# wordclock-ledboard.net
KiCad netlist of a schematic drawn in EAGLE
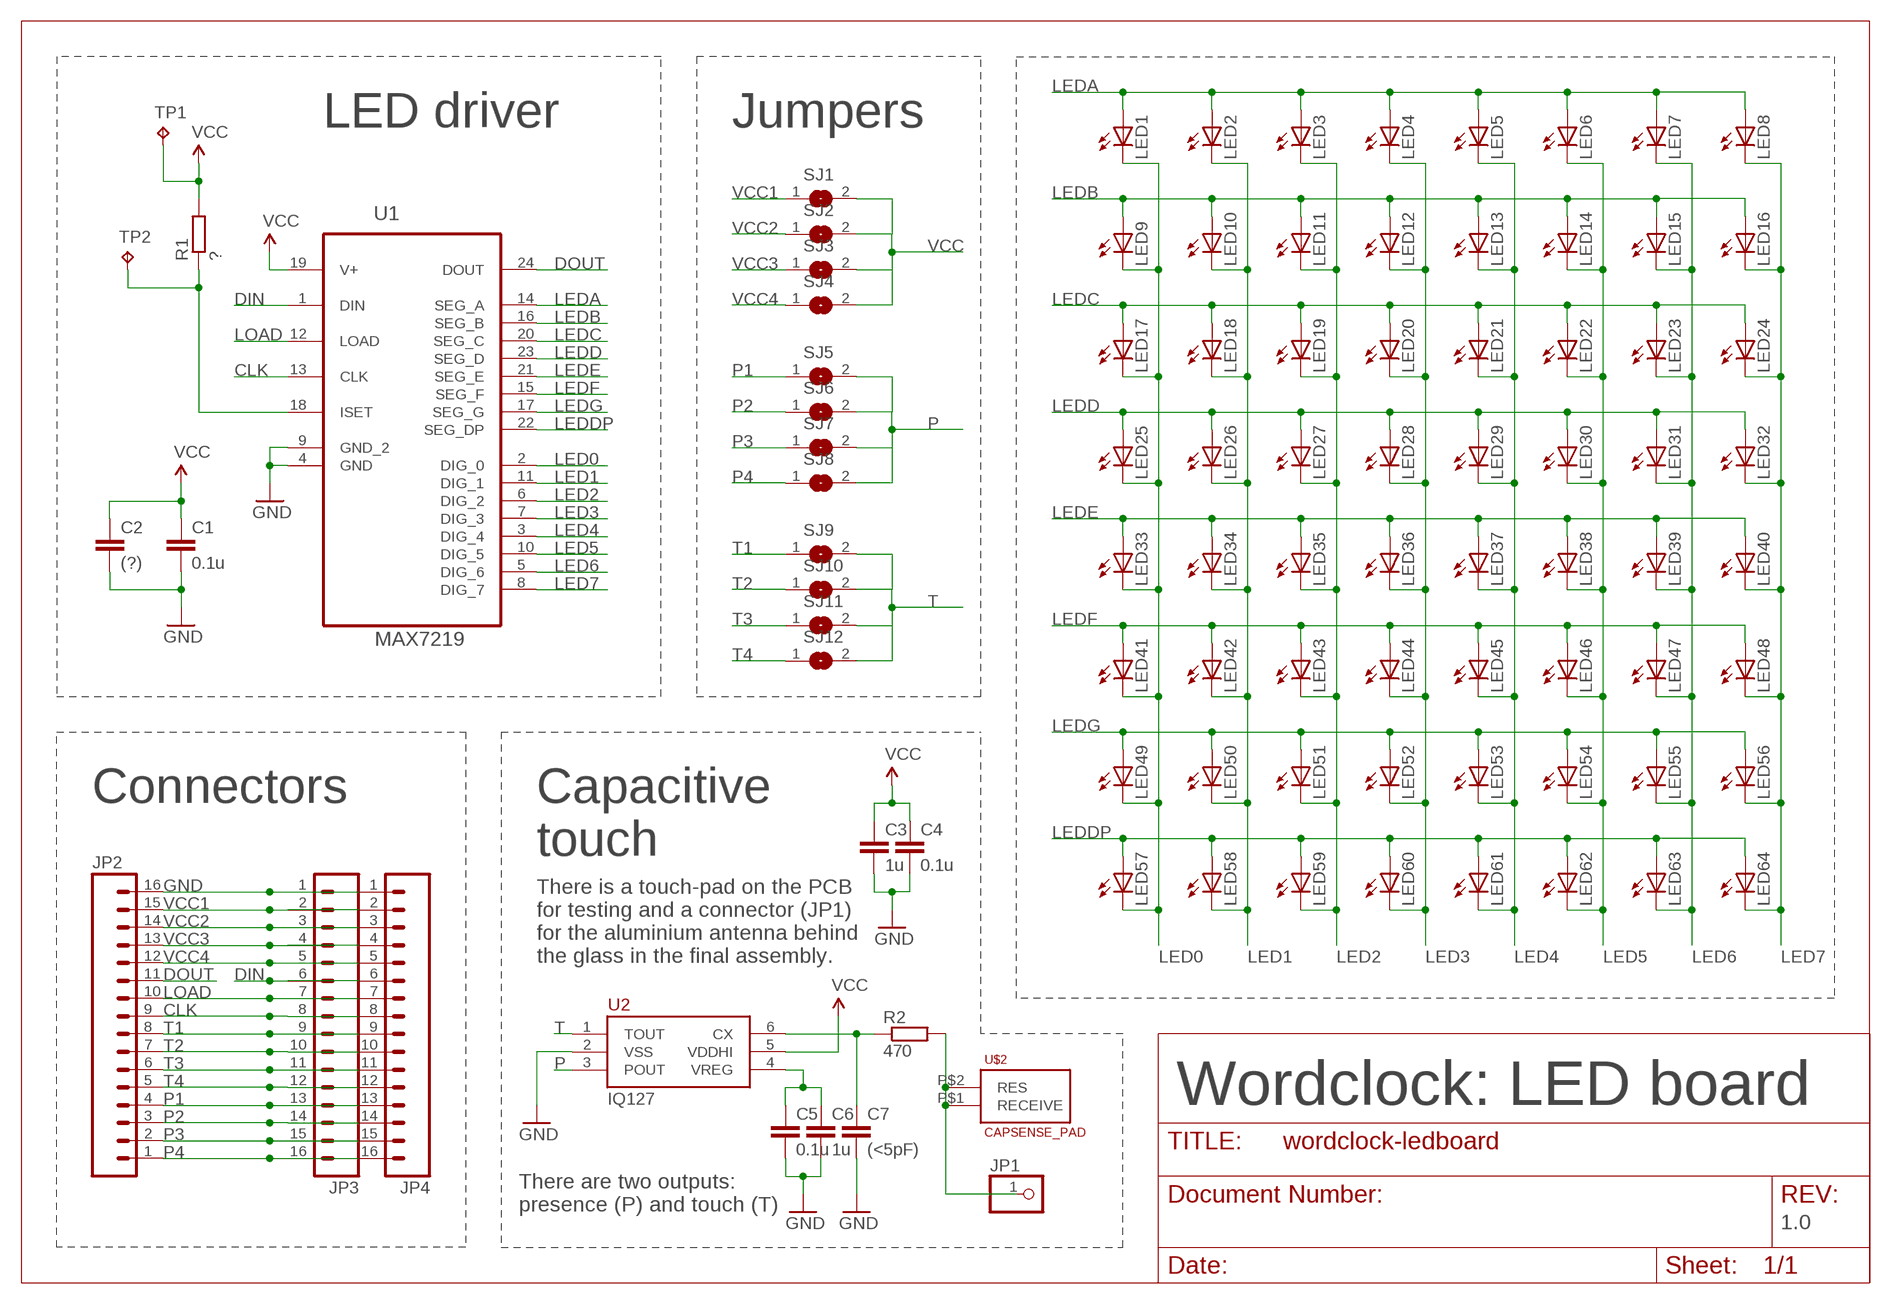
[diagram p0: schematic, sheet 1]

(export (version "E")
  (design (tool "Eeschema 10.0.6"))
  (components
    (comp (ref "C1")
      (value "0.1u")
      (footprint "eagle-import:C0805")
      (libsource (lib "eagle-import") (part "C-EUC0805"))
    )
    (comp (ref "C2")
      (value "(?)")
      (footprint "eagle-import:C0805")
      (libsource (lib "eagle-import") (part "C-EUC0805"))
    )
    (comp (ref "C3")
      (value "1u")
      (footprint "eagle-import:C0805")
      (libsource (lib "eagle-import") (part "C-EUC0805"))
    )
    (comp (ref "C4")
      (value "0.1u")
      (footprint "eagle-import:C0805")
      (libsource (lib "eagle-import") (part "C-EUC0805"))
    )
    (comp (ref "C5")
      (value "0.1u")
      (footprint "eagle-import:C0805")
      (libsource (lib "eagle-import") (part "C-EUC0805"))
    )
    (comp (ref "C6")
      (value "1u")
      (footprint "eagle-import:C0805")
      (libsource (lib "eagle-import") (part "C-EUC0805"))
    )
    (comp (ref "C7")
      (value "(<5pF)")
      (footprint "eagle-import:C0805")
      (libsource (lib "eagle-import") (part "C-EUC0805"))
    )
    (comp (ref "JP1")
      (value "PINHD-1X1")
      (footprint "eagle-import:1X01")
      (libsource (lib "eagle-import") (part "PINHD-1X1"))
    )
    (comp (ref "JP2")
      (value "M161X16_NO_SILK")
      (footprint "eagle-import:1X16_NO_SILK")
      (libsource (lib "eagle-import") (part "M161X16_NO_SILK"))
    )
    (comp (ref "JP3")
      (value "M161X16_NO_SILK")
      (footprint "eagle-import:1X16_NO_SILK")
      (libsource (lib "eagle-import") (part "M161X16_NO_SILK"))
    )
    (comp (ref "JP4")
      (value "M161X16_NO_SILK")
      (footprint "eagle-import:1X16_NO_SILK")
      (libsource (lib "eagle-import") (part "M161X16_NO_SILK"))
    )
    (comp (ref "LED1")
      (value "LEDKA-3528ASYC")
      (footprint "eagle-import:KA-3528ASYC")
      (libsource (lib "eagle-import") (part "LEDKA-3528ASYC"))
    )
    (comp (ref "LED2")
      (value "LEDKA-3528ASYC")
      (footprint "eagle-import:KA-3528ASYC")
      (libsource (lib "eagle-import") (part "LEDKA-3528ASYC"))
    )
    (comp (ref "LED3")
      (value "LEDKA-3528ASYC")
      (footprint "eagle-import:KA-3528ASYC")
      (libsource (lib "eagle-import") (part "LEDKA-3528ASYC"))
    )
    (comp (ref "LED4")
      (value "LEDKA-3528ASYC")
      (footprint "eagle-import:KA-3528ASYC")
      (libsource (lib "eagle-import") (part "LEDKA-3528ASYC"))
    )
    (comp (ref "LED5")
      (value "LEDKA-3528ASYC")
      (footprint "eagle-import:KA-3528ASYC")
      (libsource (lib "eagle-import") (part "LEDKA-3528ASYC"))
    )
    (comp (ref "LED6")
      (value "LEDKA-3528ASYC")
      (footprint "eagle-import:KA-3528ASYC")
      (libsource (lib "eagle-import") (part "LEDKA-3528ASYC"))
    )
    (comp (ref "LED7")
      (value "LEDKA-3528ASYC")
      (footprint "eagle-import:KA-3528ASYC")
      (libsource (lib "eagle-import") (part "LEDKA-3528ASYC"))
    )
    (comp (ref "LED8")
      (value "LEDKA-3528ASYC")
      (footprint "eagle-import:KA-3528ASYC")
      (libsource (lib "eagle-import") (part "LEDKA-3528ASYC"))
    )
    (comp (ref "LED9")
      (value "LEDKA-3528ASYC")
      (footprint "eagle-import:KA-3528ASYC")
      (libsource (lib "eagle-import") (part "LEDKA-3528ASYC"))
    )
    (comp (ref "LED10")
      (value "LEDKA-3528ASYC")
      (footprint "eagle-import:KA-3528ASYC")
      (libsource (lib "eagle-import") (part "LEDKA-3528ASYC"))
    )
    (comp (ref "LED11")
      (value "LEDKA-3528ASYC")
      (footprint "eagle-import:KA-3528ASYC")
      (libsource (lib "eagle-import") (part "LEDKA-3528ASYC"))
    )
    (comp (ref "LED12")
      (value "LEDKA-3528ASYC")
      (footprint "eagle-import:KA-3528ASYC")
      (libsource (lib "eagle-import") (part "LEDKA-3528ASYC"))
    )
    (comp (ref "LED13")
      (value "LEDKA-3528ASYC")
      (footprint "eagle-import:KA-3528ASYC")
      (libsource (lib "eagle-import") (part "LEDKA-3528ASYC"))
    )
    (comp (ref "LED14")
      (value "LEDKA-3528ASYC")
      (footprint "eagle-import:KA-3528ASYC")
      (libsource (lib "eagle-import") (part "LEDKA-3528ASYC"))
    )
    (comp (ref "LED15")
      (value "LEDKA-3528ASYC")
      (footprint "eagle-import:KA-3528ASYC")
      (libsource (lib "eagle-import") (part "LEDKA-3528ASYC"))
    )
    (comp (ref "LED16")
      (value "LEDKA-3528ASYC")
      (footprint "eagle-import:KA-3528ASYC")
      (libsource (lib "eagle-import") (part "LEDKA-3528ASYC"))
    )
    (comp (ref "LED17")
      (value "LEDKA-3528ASYC")
      (footprint "eagle-import:KA-3528ASYC")
      (libsource (lib "eagle-import") (part "LEDKA-3528ASYC"))
    )
    (comp (ref "LED18")
      (value "LEDKA-3528ASYC")
      (footprint "eagle-import:KA-3528ASYC")
      (libsource (lib "eagle-import") (part "LEDKA-3528ASYC"))
    )
    (comp (ref "LED19")
      (value "LEDKA-3528ASYC")
      (footprint "eagle-import:KA-3528ASYC")
      (libsource (lib "eagle-import") (part "LEDKA-3528ASYC"))
    )
    (comp (ref "LED20")
      (value "LEDKA-3528ASYC")
      (footprint "eagle-import:KA-3528ASYC")
      (libsource (lib "eagle-import") (part "LEDKA-3528ASYC"))
    )
    (comp (ref "LED21")
      (value "LEDKA-3528ASYC")
      (footprint "eagle-import:KA-3528ASYC")
      (libsource (lib "eagle-import") (part "LEDKA-3528ASYC"))
    )
    (comp (ref "LED22")
      (value "LEDKA-3528ASYC")
      (footprint "eagle-import:KA-3528ASYC")
      (libsource (lib "eagle-import") (part "LEDKA-3528ASYC"))
    )
    (comp (ref "LED23")
      (value "LEDKA-3528ASYC")
      (footprint "eagle-import:KA-3528ASYC")
      (libsource (lib "eagle-import") (part "LEDKA-3528ASYC"))
    )
    (comp (ref "LED24")
      (value "LEDKA-3528ASYC")
      (footprint "eagle-import:KA-3528ASYC")
      (libsource (lib "eagle-import") (part "LEDKA-3528ASYC"))
    )
    (comp (ref "LED25")
      (value "LEDKA-3528ASYC")
      (footprint "eagle-import:KA-3528ASYC")
      (libsource (lib "eagle-import") (part "LEDKA-3528ASYC"))
    )
    (comp (ref "LED26")
      (value "LEDKA-3528ASYC")
      (footprint "eagle-import:KA-3528ASYC")
      (libsource (lib "eagle-import") (part "LEDKA-3528ASYC"))
    )
    (comp (ref "LED27")
      (value "LEDKA-3528ASYC")
      (footprint "eagle-import:KA-3528ASYC")
      (libsource (lib "eagle-import") (part "LEDKA-3528ASYC"))
    )
    (comp (ref "LED28")
      (value "LEDKA-3528ASYC")
      (footprint "eagle-import:KA-3528ASYC")
      (libsource (lib "eagle-import") (part "LEDKA-3528ASYC"))
    )
    (comp (ref "LED29")
      (value "LEDKA-3528ASYC")
      (footprint "eagle-import:KA-3528ASYC")
      (libsource (lib "eagle-import") (part "LEDKA-3528ASYC"))
    )
    (comp (ref "LED30")
      (value "LEDKA-3528ASYC")
      (footprint "eagle-import:KA-3528ASYC")
      (libsource (lib "eagle-import") (part "LEDKA-3528ASYC"))
    )
    (comp (ref "LED31")
      (value "LEDKA-3528ASYC")
      (footprint "eagle-import:KA-3528ASYC")
      (libsource (lib "eagle-import") (part "LEDKA-3528ASYC"))
    )
    (comp (ref "LED32")
      (value "LEDKA-3528ASYC")
      (footprint "eagle-import:KA-3528ASYC")
      (libsource (lib "eagle-import") (part "LEDKA-3528ASYC"))
    )
    (comp (ref "LED33")
      (value "LEDKA-3528ASYC")
      (footprint "eagle-import:KA-3528ASYC")
      (libsource (lib "eagle-import") (part "LEDKA-3528ASYC"))
    )
    (comp (ref "LED34")
      (value "LEDKA-3528ASYC")
      (footprint "eagle-import:KA-3528ASYC")
      (libsource (lib "eagle-import") (part "LEDKA-3528ASYC"))
    )
    (comp (ref "LED35")
      (value "LEDKA-3528ASYC")
      (footprint "eagle-import:KA-3528ASYC")
      (libsource (lib "eagle-import") (part "LEDKA-3528ASYC"))
    )
    (comp (ref "LED36")
      (value "LEDKA-3528ASYC")
      (footprint "eagle-import:KA-3528ASYC")
      (libsource (lib "eagle-import") (part "LEDKA-3528ASYC"))
    )
    (comp (ref "LED37")
      (value "LEDKA-3528ASYC")
      (footprint "eagle-import:KA-3528ASYC")
      (libsource (lib "eagle-import") (part "LEDKA-3528ASYC"))
    )
    (comp (ref "LED38")
      (value "LEDKA-3528ASYC")
      (footprint "eagle-import:KA-3528ASYC")
      (libsource (lib "eagle-import") (part "LEDKA-3528ASYC"))
    )
    (comp (ref "LED39")
      (value "LEDKA-3528ASYC")
      (footprint "eagle-import:KA-3528ASYC")
      (libsource (lib "eagle-import") (part "LEDKA-3528ASYC"))
    )
    (comp (ref "LED40")
      (value "LEDKA-3528ASYC")
      (footprint "eagle-import:KA-3528ASYC")
      (libsource (lib "eagle-import") (part "LEDKA-3528ASYC"))
    )
    (comp (ref "LED41")
      (value "LEDKA-3528ASYC")
      (footprint "eagle-import:KA-3528ASYC")
      (libsource (lib "eagle-import") (part "LEDKA-3528ASYC"))
    )
    (comp (ref "LED42")
      (value "LEDKA-3528ASYC")
      (footprint "eagle-import:KA-3528ASYC")
      (libsource (lib "eagle-import") (part "LEDKA-3528ASYC"))
    )
    (comp (ref "LED43")
      (value "LEDKA-3528ASYC")
      (footprint "eagle-import:KA-3528ASYC")
      (libsource (lib "eagle-import") (part "LEDKA-3528ASYC"))
    )
    (comp (ref "LED44")
      (value "LEDKA-3528ASYC")
      (footprint "eagle-import:KA-3528ASYC")
      (libsource (lib "eagle-import") (part "LEDKA-3528ASYC"))
    )
    (comp (ref "LED45")
      (value "LEDKA-3528ASYC")
      (footprint "eagle-import:KA-3528ASYC")
      (libsource (lib "eagle-import") (part "LEDKA-3528ASYC"))
    )
    (comp (ref "LED46")
      (value "LEDKA-3528ASYC")
      (footprint "eagle-import:KA-3528ASYC")
      (libsource (lib "eagle-import") (part "LEDKA-3528ASYC"))
    )
    (comp (ref "LED47")
      (value "LEDKA-3528ASYC")
      (footprint "eagle-import:KA-3528ASYC")
      (libsource (lib "eagle-import") (part "LEDKA-3528ASYC"))
    )
    (comp (ref "LED48")
      (value "LEDKA-3528ASYC")
      (footprint "eagle-import:KA-3528ASYC")
      (libsource (lib "eagle-import") (part "LEDKA-3528ASYC"))
    )
    (comp (ref "LED49")
      (value "LEDKA-3528ASYC")
      (footprint "eagle-import:KA-3528ASYC")
      (libsource (lib "eagle-import") (part "LEDKA-3528ASYC"))
    )
    (comp (ref "LED50")
      (value "LEDKA-3528ASYC")
      (footprint "eagle-import:KA-3528ASYC")
      (libsource (lib "eagle-import") (part "LEDKA-3528ASYC"))
    )
    (comp (ref "LED51")
      (value "LEDKA-3528ASYC")
      (footprint "eagle-import:KA-3528ASYC")
      (libsource (lib "eagle-import") (part "LEDKA-3528ASYC"))
    )
    (comp (ref "LED52")
      (value "LEDKA-3528ASYC")
      (footprint "eagle-import:KA-3528ASYC")
      (libsource (lib "eagle-import") (part "LEDKA-3528ASYC"))
    )
    (comp (ref "LED53")
      (value "LEDKA-3528ASYC")
      (footprint "eagle-import:KA-3528ASYC")
      (libsource (lib "eagle-import") (part "LEDKA-3528ASYC"))
    )
    (comp (ref "LED54")
      (value "LEDKA-3528ASYC")
      (footprint "eagle-import:KA-3528ASYC")
      (libsource (lib "eagle-import") (part "LEDKA-3528ASYC"))
    )
    (comp (ref "LED55")
      (value "LEDKA-3528ASYC")
      (footprint "eagle-import:KA-3528ASYC")
      (libsource (lib "eagle-import") (part "LEDKA-3528ASYC"))
    )
    (comp (ref "LED56")
      (value "LEDKA-3528ASYC")
      (footprint "eagle-import:KA-3528ASYC")
      (libsource (lib "eagle-import") (part "LEDKA-3528ASYC"))
    )
    (comp (ref "LED57")
      (value "LEDKA-3528ASYC")
      (footprint "eagle-import:KA-3528ASYC")
      (libsource (lib "eagle-import") (part "LEDKA-3528ASYC"))
    )
    (comp (ref "LED58")
      (value "LEDKA-3528ASYC")
      (footprint "eagle-import:KA-3528ASYC")
      (libsource (lib "eagle-import") (part "LEDKA-3528ASYC"))
    )
    (comp (ref "LED59")
      (value "LEDKA-3528ASYC")
      (footprint "eagle-import:KA-3528ASYC")
      (libsource (lib "eagle-import") (part "LEDKA-3528ASYC"))
    )
    (comp (ref "LED60")
      (value "LEDKA-3528ASYC")
      (footprint "eagle-import:KA-3528ASYC")
      (libsource (lib "eagle-import") (part "LEDKA-3528ASYC"))
    )
    (comp (ref "LED61")
      (value "LEDKA-3528ASYC")
      (footprint "eagle-import:KA-3528ASYC")
      (libsource (lib "eagle-import") (part "LEDKA-3528ASYC"))
    )
    (comp (ref "LED62")
      (value "LEDKA-3528ASYC")
      (footprint "eagle-import:KA-3528ASYC")
      (libsource (lib "eagle-import") (part "LEDKA-3528ASYC"))
    )
    (comp (ref "LED63")
      (value "LEDKA-3528ASYC")
      (footprint "eagle-import:KA-3528ASYC")
      (libsource (lib "eagle-import") (part "LEDKA-3528ASYC"))
    )
    (comp (ref "LED64")
      (value "LEDKA-3528ASYC")
      (footprint "eagle-import:KA-3528ASYC")
      (libsource (lib "eagle-import") (part "LEDKA-3528ASYC"))
    )
    (comp (ref "R1")
      (value "?")
      (footprint "eagle-import:R0603")
      (libsource (lib "eagle-import") (part "R-EU_R0603"))
    )
    (comp (ref "R2")
      (value "470")
      (footprint "eagle-import:R0603")
      (libsource (lib "eagle-import") (part "R-EU_R0603"))
    )
    (comp (ref "SJ1")
      (value "SJW")
      (footprint "eagle-import:SJW")
      (libsource (lib "eagle-import") (part "SJW"))
    )
    (comp (ref "SJ2")
      (value "SJW")
      (footprint "eagle-import:SJW")
      (libsource (lib "eagle-import") (part "SJW"))
    )
    (comp (ref "SJ3")
      (value "SJW")
      (footprint "eagle-import:SJW")
      (libsource (lib "eagle-import") (part "SJW"))
    )
    (comp (ref "SJ4")
      (value "SJW")
      (footprint "eagle-import:SJW")
      (libsource (lib "eagle-import") (part "SJW"))
    )
    (comp (ref "SJ5")
      (value "SJW")
      (footprint "eagle-import:SJW")
      (libsource (lib "eagle-import") (part "SJW"))
    )
    (comp (ref "SJ6")
      (value "SJW")
      (footprint "eagle-import:SJW")
      (libsource (lib "eagle-import") (part "SJW"))
    )
    (comp (ref "SJ7")
      (value "SJW")
      (footprint "eagle-import:SJW")
      (libsource (lib "eagle-import") (part "SJW"))
    )
    (comp (ref "SJ8")
      (value "SJW")
      (footprint "eagle-import:SJW")
      (libsource (lib "eagle-import") (part "SJW"))
    )
    (comp (ref "SJ9")
      (value "SJW")
      (footprint "eagle-import:SJW")
      (libsource (lib "eagle-import") (part "SJW"))
    )
    (comp (ref "SJ10")
      (value "SJW")
      (footprint "eagle-import:SJW")
      (libsource (lib "eagle-import") (part "SJW"))
    )
    (comp (ref "SJ11")
      (value "SJW")
      (footprint "eagle-import:SJW")
      (libsource (lib "eagle-import") (part "SJW"))
    )
    (comp (ref "SJ12")
      (value "SJW")
      (footprint "eagle-import:SJW")
      (libsource (lib "eagle-import") (part "SJW"))
    )
    (comp (ref "TP1")
      (value "TPTP20R")
      (footprint "eagle-import:TP20R")
      (libsource (lib "eagle-import") (part "TPTP20R"))
    )
    (comp (ref "TP2")
      (value "TPTP20R")
      (footprint "eagle-import:TP20R")
      (libsource (lib "eagle-import") (part "TPTP20R"))
    )
    (comp (ref "U$2")
      (value "CAPSENSE_PAD")
      (footprint "eagle-import:CAPSENSE_PAD")
      (libsource (lib "eagle-import") (part "CAPSENSE_PAD"))
    )
    (comp (ref "U1")
      (value "MAX7219")
      (footprint "eagle-import:SOIC127P1032X265-24N")
      (fields (field (name "MPN") "MAX7219CWG+T"))
      (libsource (lib "eagle-import") (part "MAX7219CWG+T"))
    )
    (comp (ref "U2")
      (value "IQ127")
      (footprint "eagle-import:TSOT-23-6")
      (libsource (lib "eagle-import") (part "IQ127"))
    )
  )
  (nets
    (net (code "1") (name "/CLK") (class "Default")
      (node (ref "JP2") (pin "9") (pinfunction "9_9") (pintype "passive"))
      (node (ref "JP3") (pin "8") (pinfunction "8_8") (pintype "passive"))
      (node (ref "JP4") (pin "8") (pinfunction "8_8") (pintype "passive"))
      (node (ref "U1") (pin "13") (pinfunction "CLK_13") (pintype "input"))
    )
    (net (code "2") (name "/DIN") (class "Default")
      (node (ref "JP3") (pin "6") (pinfunction "6_6") (pintype "passive"))
      (node (ref "JP4") (pin "6") (pinfunction "6_6") (pintype "passive"))
      (node (ref "U1") (pin "1") (pinfunction "DIN_1") (pintype "input"))
    )
    (net (code "3") (name "/DOUT") (class "Default")
      (node (ref "JP2") (pin "11") (pinfunction "11_11") (pintype "passive"))
      (node (ref "U1") (pin "24") (pinfunction "DOUT_24") (pintype "output"))
    )
    (net (code "4") (name "/LED0") (class "Default")
      (node (ref "LED1") (pin "C") (pinfunction "C_C") (pintype "passive"))
      (node (ref "LED17") (pin "C") (pinfunction "C_C") (pintype "passive"))
      (node (ref "LED25") (pin "C") (pinfunction "C_C") (pintype "passive"))
      (node (ref "LED33") (pin "C") (pinfunction "C_C") (pintype "passive"))
      (node (ref "LED41") (pin "C") (pinfunction "C_C") (pintype "passive"))
      (node (ref "LED49") (pin "C") (pinfunction "C_C") (pintype "passive"))
      (node (ref "LED57") (pin "C") (pinfunction "C_C") (pintype "passive"))
      (node (ref "LED9") (pin "C") (pinfunction "C_C") (pintype "passive"))
      (node (ref "U1") (pin "2") (pinfunction "DIG_0_2") (pintype "output"))
    )
    (net (code "5") (name "/LED1") (class "Default")
      (node (ref "LED10") (pin "C") (pinfunction "C_C") (pintype "passive"))
      (node (ref "LED18") (pin "C") (pinfunction "C_C") (pintype "passive"))
      (node (ref "LED2") (pin "C") (pinfunction "C_C") (pintype "passive"))
      (node (ref "LED26") (pin "C") (pinfunction "C_C") (pintype "passive"))
      (node (ref "LED34") (pin "C") (pinfunction "C_C") (pintype "passive"))
      (node (ref "LED42") (pin "C") (pinfunction "C_C") (pintype "passive"))
      (node (ref "LED50") (pin "C") (pinfunction "C_C") (pintype "passive"))
      (node (ref "LED58") (pin "C") (pinfunction "C_C") (pintype "passive"))
      (node (ref "U1") (pin "11") (pinfunction "DIG_1_11") (pintype "output"))
    )
    (net (code "6") (name "/LED2") (class "Default")
      (node (ref "LED11") (pin "C") (pinfunction "C_C") (pintype "passive"))
      (node (ref "LED19") (pin "C") (pinfunction "C_C") (pintype "passive"))
      (node (ref "LED27") (pin "C") (pinfunction "C_C") (pintype "passive"))
      (node (ref "LED3") (pin "C") (pinfunction "C_C") (pintype "passive"))
      (node (ref "LED35") (pin "C") (pinfunction "C_C") (pintype "passive"))
      (node (ref "LED43") (pin "C") (pinfunction "C_C") (pintype "passive"))
      (node (ref "LED51") (pin "C") (pinfunction "C_C") (pintype "passive"))
      (node (ref "LED59") (pin "C") (pinfunction "C_C") (pintype "passive"))
      (node (ref "U1") (pin "6") (pinfunction "DIG_2_6") (pintype "output"))
    )
    (net (code "7") (name "/LED3") (class "Default")
      (node (ref "LED12") (pin "C") (pinfunction "C_C") (pintype "passive"))
      (node (ref "LED20") (pin "C") (pinfunction "C_C") (pintype "passive"))
      (node (ref "LED28") (pin "C") (pinfunction "C_C") (pintype "passive"))
      (node (ref "LED36") (pin "C") (pinfunction "C_C") (pintype "passive"))
      (node (ref "LED4") (pin "C") (pinfunction "C_C") (pintype "passive"))
      (node (ref "LED44") (pin "C") (pinfunction "C_C") (pintype "passive"))
      (node (ref "LED52") (pin "C") (pinfunction "C_C") (pintype "passive"))
      (node (ref "LED60") (pin "C") (pinfunction "C_C") (pintype "passive"))
      (node (ref "U1") (pin "7") (pinfunction "DIG_3_7") (pintype "output"))
    )
    (net (code "8") (name "/LED4") (class "Default")
      (node (ref "LED13") (pin "C") (pinfunction "C_C") (pintype "passive"))
      (node (ref "LED21") (pin "C") (pinfunction "C_C") (pintype "passive"))
      (node (ref "LED29") (pin "C") (pinfunction "C_C") (pintype "passive"))
      (node (ref "LED37") (pin "C") (pinfunction "C_C") (pintype "passive"))
      (node (ref "LED45") (pin "C") (pinfunction "C_C") (pintype "passive"))
      (node (ref "LED5") (pin "C") (pinfunction "C_C") (pintype "passive"))
      (node (ref "LED53") (pin "C") (pinfunction "C_C") (pintype "passive"))
      (node (ref "LED61") (pin "C") (pinfunction "C_C") (pintype "passive"))
      (node (ref "U1") (pin "3") (pinfunction "DIG_4_3") (pintype "output"))
    )
    (net (code "9") (name "/LED5") (class "Default")
      (node (ref "LED14") (pin "C") (pinfunction "C_C") (pintype "passive"))
      (node (ref "LED22") (pin "C") (pinfunction "C_C") (pintype "passive"))
      (node (ref "LED30") (pin "C") (pinfunction "C_C") (pintype "passive"))
      (node (ref "LED38") (pin "C") (pinfunction "C_C") (pintype "passive"))
      (node (ref "LED46") (pin "C") (pinfunction "C_C") (pintype "passive"))
      (node (ref "LED54") (pin "C") (pinfunction "C_C") (pintype "passive"))
      (node (ref "LED6") (pin "C") (pinfunction "C_C") (pintype "passive"))
      (node (ref "LED62") (pin "C") (pinfunction "C_C") (pintype "passive"))
      (node (ref "U1") (pin "10") (pinfunction "DIG_5_10") (pintype "output"))
    )
    (net (code "10") (name "/LED6") (class "Default")
      (node (ref "LED15") (pin "C") (pinfunction "C_C") (pintype "passive"))
      (node (ref "LED23") (pin "C") (pinfunction "C_C") (pintype "passive"))
      (node (ref "LED31") (pin "C") (pinfunction "C_C") (pintype "passive"))
      (node (ref "LED39") (pin "C") (pinfunction "C_C") (pintype "passive"))
      (node (ref "LED47") (pin "C") (pinfunction "C_C") (pintype "passive"))
      (node (ref "LED55") (pin "C") (pinfunction "C_C") (pintype "passive"))
      (node (ref "LED63") (pin "C") (pinfunction "C_C") (pintype "passive"))
      (node (ref "LED7") (pin "C") (pinfunction "C_C") (pintype "passive"))
      (node (ref "U1") (pin "5") (pinfunction "DIG_6_5") (pintype "output"))
    )
    (net (code "11") (name "/LED7") (class "Default")
      (node (ref "LED16") (pin "C") (pinfunction "C_C") (pintype "passive"))
      (node (ref "LED24") (pin "C") (pinfunction "C_C") (pintype "passive"))
      (node (ref "LED32") (pin "C") (pinfunction "C_C") (pintype "passive"))
      (node (ref "LED40") (pin "C") (pinfunction "C_C") (pintype "passive"))
      (node (ref "LED48") (pin "C") (pinfunction "C_C") (pintype "passive"))
      (node (ref "LED56") (pin "C") (pinfunction "C_C") (pintype "passive"))
      (node (ref "LED64") (pin "C") (pinfunction "C_C") (pintype "passive"))
      (node (ref "LED8") (pin "C") (pinfunction "C_C") (pintype "passive"))
      (node (ref "U1") (pin "8") (pinfunction "DIG_7_8") (pintype "output"))
    )
    (net (code "12") (name "/LEDA") (class "Default")
      (node (ref "LED1") (pin "A") (pinfunction "A_A") (pintype "passive"))
      (node (ref "LED2") (pin "A") (pinfunction "A_A") (pintype "passive"))
      (node (ref "LED3") (pin "A") (pinfunction "A_A") (pintype "passive"))
      (node (ref "LED4") (pin "A") (pinfunction "A_A") (pintype "passive"))
      (node (ref "LED5") (pin "A") (pinfunction "A_A") (pintype "passive"))
      (node (ref "LED6") (pin "A") (pinfunction "A_A") (pintype "passive"))
      (node (ref "LED7") (pin "A") (pinfunction "A_A") (pintype "passive"))
      (node (ref "LED8") (pin "A") (pinfunction "A_A") (pintype "passive"))
      (node (ref "U1") (pin "14") (pinfunction "SEG_A_14") (pintype "output"))
    )
    (net (code "13") (name "/LEDB") (class "Default")
      (node (ref "LED10") (pin "A") (pinfunction "A_A") (pintype "passive"))
      (node (ref "LED11") (pin "A") (pinfunction "A_A") (pintype "passive"))
      (node (ref "LED12") (pin "A") (pinfunction "A_A") (pintype "passive"))
      (node (ref "LED13") (pin "A") (pinfunction "A_A") (pintype "passive"))
      (node (ref "LED14") (pin "A") (pinfunction "A_A") (pintype "passive"))
      (node (ref "LED15") (pin "A") (pinfunction "A_A") (pintype "passive"))
      (node (ref "LED16") (pin "A") (pinfunction "A_A") (pintype "passive"))
      (node (ref "LED9") (pin "A") (pinfunction "A_A") (pintype "passive"))
      (node (ref "U1") (pin "16") (pinfunction "SEG_B_16") (pintype "output"))
    )
    (net (code "14") (name "/LEDC") (class "Default")
      (node (ref "LED17") (pin "A") (pinfunction "A_A") (pintype "passive"))
      (node (ref "LED18") (pin "A") (pinfunction "A_A") (pintype "passive"))
      (node (ref "LED19") (pin "A") (pinfunction "A_A") (pintype "passive"))
      (node (ref "LED20") (pin "A") (pinfunction "A_A") (pintype "passive"))
      (node (ref "LED21") (pin "A") (pinfunction "A_A") (pintype "passive"))
      (node (ref "LED22") (pin "A") (pinfunction "A_A") (pintype "passive"))
      (node (ref "LED23") (pin "A") (pinfunction "A_A") (pintype "passive"))
      (node (ref "LED24") (pin "A") (pinfunction "A_A") (pintype "passive"))
      (node (ref "U1") (pin "20") (pinfunction "SEG_C_20") (pintype "output"))
    )
    (net (code "15") (name "/LEDD") (class "Default")
      (node (ref "LED25") (pin "A") (pinfunction "A_A") (pintype "passive"))
      (node (ref "LED26") (pin "A") (pinfunction "A_A") (pintype "passive"))
      (node (ref "LED27") (pin "A") (pinfunction "A_A") (pintype "passive"))
      (node (ref "LED28") (pin "A") (pinfunction "A_A") (pintype "passive"))
      (node (ref "LED29") (pin "A") (pinfunction "A_A") (pintype "passive"))
      (node (ref "LED30") (pin "A") (pinfunction "A_A") (pintype "passive"))
      (node (ref "LED31") (pin "A") (pinfunction "A_A") (pintype "passive"))
      (node (ref "LED32") (pin "A") (pinfunction "A_A") (pintype "passive"))
      (node (ref "U1") (pin "23") (pinfunction "SEG_D_23") (pintype "output"))
    )
    (net (code "16") (name "/LEDDP") (class "Default")
      (node (ref "LED57") (pin "A") (pinfunction "A_A") (pintype "passive"))
      (node (ref "LED58") (pin "A") (pinfunction "A_A") (pintype "passive"))
      (node (ref "LED59") (pin "A") (pinfunction "A_A") (pintype "passive"))
      (node (ref "LED60") (pin "A") (pinfunction "A_A") (pintype "passive"))
      (node (ref "LED61") (pin "A") (pinfunction "A_A") (pintype "passive"))
      (node (ref "LED62") (pin "A") (pinfunction "A_A") (pintype "passive"))
      (node (ref "LED63") (pin "A") (pinfunction "A_A") (pintype "passive"))
      (node (ref "LED64") (pin "A") (pinfunction "A_A") (pintype "passive"))
      (node (ref "U1") (pin "22") (pinfunction "SEG_DP_22") (pintype "output"))
    )
    (net (code "17") (name "/LEDE") (class "Default")
      (node (ref "LED33") (pin "A") (pinfunction "A_A") (pintype "passive"))
      (node (ref "LED34") (pin "A") (pinfunction "A_A") (pintype "passive"))
      (node (ref "LED35") (pin "A") (pinfunction "A_A") (pintype "passive"))
      (node (ref "LED36") (pin "A") (pinfunction "A_A") (pintype "passive"))
      (node (ref "LED37") (pin "A") (pinfunction "A_A") (pintype "passive"))
      (node (ref "LED38") (pin "A") (pinfunction "A_A") (pintype "passive"))
      (node (ref "LED39") (pin "A") (pinfunction "A_A") (pintype "passive"))
      (node (ref "LED40") (pin "A") (pinfunction "A_A") (pintype "passive"))
      (node (ref "U1") (pin "21") (pinfunction "SEG_E_21") (pintype "output"))
    )
    (net (code "18") (name "/LEDF") (class "Default")
      (node (ref "LED41") (pin "A") (pinfunction "A_A") (pintype "passive"))
      (node (ref "LED42") (pin "A") (pinfunction "A_A") (pintype "passive"))
      (node (ref "LED43") (pin "A") (pinfunction "A_A") (pintype "passive"))
      (node (ref "LED44") (pin "A") (pinfunction "A_A") (pintype "passive"))
      (node (ref "LED45") (pin "A") (pinfunction "A_A") (pintype "passive"))
      (node (ref "LED46") (pin "A") (pinfunction "A_A") (pintype "passive"))
      (node (ref "LED47") (pin "A") (pinfunction "A_A") (pintype "passive"))
      (node (ref "LED48") (pin "A") (pinfunction "A_A") (pintype "passive"))
      (node (ref "U1") (pin "15") (pinfunction "SEG_F_15") (pintype "output"))
    )
    (net (code "19") (name "/LEDG") (class "Default")
      (node (ref "LED49") (pin "A") (pinfunction "A_A") (pintype "passive"))
      (node (ref "LED50") (pin "A") (pinfunction "A_A") (pintype "passive"))
      (node (ref "LED51") (pin "A") (pinfunction "A_A") (pintype "passive"))
      (node (ref "LED52") (pin "A") (pinfunction "A_A") (pintype "passive"))
      (node (ref "LED53") (pin "A") (pinfunction "A_A") (pintype "passive"))
      (node (ref "LED54") (pin "A") (pinfunction "A_A") (pintype "passive"))
      (node (ref "LED55") (pin "A") (pinfunction "A_A") (pintype "passive"))
      (node (ref "LED56") (pin "A") (pinfunction "A_A") (pintype "passive"))
      (node (ref "U1") (pin "17") (pinfunction "SEG_G_17") (pintype "output"))
    )
    (net (code "20") (name "/LOAD") (class "Default")
      (node (ref "JP2") (pin "10") (pinfunction "10_10") (pintype "passive"))
      (node (ref "JP3") (pin "7") (pinfunction "7_7") (pintype "passive"))
      (node (ref "JP4") (pin "7") (pinfunction "7_7") (pintype "passive"))
      (node (ref "U1") (pin "12") (pinfunction "LOAD_12") (pintype "input"))
    )
    (net (code "21") (name "/P") (class "Default")
      (node (ref "SJ5") (pin "2") (pinfunction "2_2") (pintype "passive"))
      (node (ref "SJ6") (pin "2") (pinfunction "2_2") (pintype "passive"))
      (node (ref "SJ7") (pin "2") (pinfunction "2_2") (pintype "passive"))
      (node (ref "SJ8") (pin "2") (pinfunction "2_2") (pintype "passive"))
      (node (ref "U2") (pin "3") (pinfunction "POUT_3") (pintype "bidirectional"))
    )
    (net (code "22") (name "/P1") (class "Default")
      (node (ref "JP2") (pin "4") (pinfunction "4_4") (pintype "passive"))
      (node (ref "JP3") (pin "13") (pinfunction "13_13") (pintype "passive"))
      (node (ref "JP4") (pin "13") (pinfunction "13_13") (pintype "passive"))
      (node (ref "SJ5") (pin "1") (pinfunction "1_1") (pintype "passive"))
    )
    (net (code "23") (name "/P2") (class "Default")
      (node (ref "JP2") (pin "3") (pinfunction "3_3") (pintype "passive"))
      (node (ref "JP3") (pin "14") (pinfunction "14_14") (pintype "passive"))
      (node (ref "JP4") (pin "14") (pinfunction "14_14") (pintype "passive"))
      (node (ref "SJ6") (pin "1") (pinfunction "1_1") (pintype "passive"))
    )
    (net (code "24") (name "/P3") (class "Default")
      (node (ref "JP2") (pin "2") (pinfunction "2_2") (pintype "passive"))
      (node (ref "JP3") (pin "15") (pinfunction "15_15") (pintype "passive"))
      (node (ref "JP4") (pin "15") (pinfunction "15_15") (pintype "passive"))
      (node (ref "SJ7") (pin "1") (pinfunction "1_1") (pintype "passive"))
    )
    (net (code "25") (name "/P4") (class "Default")
      (node (ref "JP2") (pin "1") (pinfunction "1_1") (pintype "passive"))
      (node (ref "JP3") (pin "16") (pinfunction "16_16") (pintype "passive"))
      (node (ref "JP4") (pin "16") (pinfunction "16_16") (pintype "passive"))
      (node (ref "SJ8") (pin "1") (pinfunction "1_1") (pintype "passive"))
    )
    (net (code "26") (name "/T") (class "Default")
      (node (ref "SJ10") (pin "2") (pinfunction "2_2") (pintype "passive"))
      (node (ref "SJ11") (pin "2") (pinfunction "2_2") (pintype "passive"))
      (node (ref "SJ12") (pin "2") (pinfunction "2_2") (pintype "passive"))
      (node (ref "SJ9") (pin "2") (pinfunction "2_2") (pintype "passive"))
      (node (ref "U2") (pin "1") (pinfunction "TOUT_1") (pintype "bidirectional"))
    )
    (net (code "27") (name "/T1") (class "Default")
      (node (ref "JP2") (pin "8") (pinfunction "8_8") (pintype "passive"))
      (node (ref "JP3") (pin "9") (pinfunction "9_9") (pintype "passive"))
      (node (ref "JP4") (pin "9") (pinfunction "9_9") (pintype "passive"))
      (node (ref "SJ9") (pin "1") (pinfunction "1_1") (pintype "passive"))
    )
    (net (code "28") (name "/T2") (class "Default")
      (node (ref "JP2") (pin "7") (pinfunction "7_7") (pintype "passive"))
      (node (ref "JP3") (pin "10") (pinfunction "10_10") (pintype "passive"))
      (node (ref "JP4") (pin "10") (pinfunction "10_10") (pintype "passive"))
      (node (ref "SJ10") (pin "1") (pinfunction "1_1") (pintype "passive"))
    )
    (net (code "29") (name "/T3") (class "Default")
      (node (ref "JP2") (pin "6") (pinfunction "6_6") (pintype "passive"))
      (node (ref "JP3") (pin "11") (pinfunction "11_11") (pintype "passive"))
      (node (ref "JP4") (pin "11") (pinfunction "11_11") (pintype "passive"))
      (node (ref "SJ11") (pin "1") (pinfunction "1_1") (pintype "passive"))
    )
    (net (code "30") (name "/T4") (class "Default")
      (node (ref "JP2") (pin "5") (pinfunction "5_5") (pintype "passive"))
      (node (ref "JP3") (pin "12") (pinfunction "12_12") (pintype "passive"))
      (node (ref "JP4") (pin "12") (pinfunction "12_12") (pintype "passive"))
      (node (ref "SJ12") (pin "1") (pinfunction "1_1") (pintype "passive"))
    )
    (net (code "31") (name "/VCC1") (class "Default")
      (node (ref "JP2") (pin "15") (pinfunction "15_15") (pintype "passive"))
      (node (ref "JP3") (pin "2") (pinfunction "2_2") (pintype "passive"))
      (node (ref "JP4") (pin "2") (pinfunction "2_2") (pintype "passive"))
      (node (ref "SJ1") (pin "1") (pinfunction "1_1") (pintype "passive"))
    )
    (net (code "32") (name "/VCC2") (class "Default")
      (node (ref "JP2") (pin "14") (pinfunction "14_14") (pintype "passive"))
      (node (ref "JP3") (pin "3") (pinfunction "3_3") (pintype "passive"))
      (node (ref "JP4") (pin "3") (pinfunction "3_3") (pintype "passive"))
      (node (ref "SJ2") (pin "1") (pinfunction "1_1") (pintype "passive"))
    )
    (net (code "33") (name "/VCC3") (class "Default")
      (node (ref "JP2") (pin "13") (pinfunction "13_13") (pintype "passive"))
      (node (ref "JP3") (pin "4") (pinfunction "4_4") (pintype "passive"))
      (node (ref "JP4") (pin "4") (pinfunction "4_4") (pintype "passive"))
      (node (ref "SJ3") (pin "1") (pinfunction "1_1") (pintype "passive"))
    )
    (net (code "34") (name "/VCC4") (class "Default")
      (node (ref "JP2") (pin "12") (pinfunction "12_12") (pintype "passive"))
      (node (ref "JP3") (pin "5") (pinfunction "5_5") (pintype "passive"))
      (node (ref "JP4") (pin "5") (pinfunction "5_5") (pintype "passive"))
      (node (ref "SJ4") (pin "1") (pinfunction "1_1") (pintype "passive"))
    )
    (net (code "35") (name "GND") (class "Default")
      (node (ref "C1") (pin "2") (pinfunction "2_2") (pintype "passive"))
      (node (ref "C2") (pin "2") (pinfunction "2_2") (pintype "passive"))
      (node (ref "C3") (pin "2") (pinfunction "2_2") (pintype "passive"))
      (node (ref "C4") (pin "2") (pinfunction "2_2") (pintype "passive"))
      (node (ref "C5") (pin "2") (pinfunction "2_2") (pintype "passive"))
      (node (ref "C6") (pin "2") (pinfunction "2_2") (pintype "passive"))
      (node (ref "C7") (pin "2") (pinfunction "2_2") (pintype "passive"))
      (node (ref "JP2") (pin "16") (pinfunction "16_16") (pintype "passive"))
      (node (ref "JP3") (pin "1") (pinfunction "1_1") (pintype "passive"))
      (node (ref "JP4") (pin "1") (pinfunction "1_1") (pintype "passive"))
      (node (ref "U1") (pin "4") (pinfunction "GND_4") (pintype "passive"))
      (node (ref "U1") (pin "9") (pinfunction "GND_2_9") (pintype "passive"))
      (node (ref "U2") (pin "2") (pinfunction "VSS_2") (pintype "bidirectional"))
    )
    (net (code "36") (name "Net-(U$2-RECEIVE)") (class "Default")
      (node (ref "JP1") (pin "1") (pinfunction "1_1") (pintype "passive"))
      (node (ref "R2") (pin "2") (pinfunction "2_2") (pintype "passive"))
      (node (ref "U$2") (pin "P$1") (pinfunction "RECEIVE_P$1") (pintype "bidirectional"))
      (node (ref "U$2") (pin "P$2") (pinfunction "RES_P$2") (pintype "bidirectional"))
    )
    (net (code "37") (name "Net-(U1-ISET)") (class "Default")
      (node (ref "R1") (pin "1") (pinfunction "1_1") (pintype "passive"))
      (node (ref "TP2") (pin "TP") (pinfunction "TP_TP") (pintype "input"))
      (node (ref "U1") (pin "18") (pinfunction "ISET_18") (pintype "input"))
    )
    (net (code "38") (name "Net-(U2-CX)") (class "Default")
      (node (ref "C7") (pin "1") (pinfunction "1_1") (pintype "passive"))
      (node (ref "R2") (pin "1") (pinfunction "1_1") (pintype "passive"))
      (node (ref "U2") (pin "6") (pinfunction "CX_6") (pintype "bidirectional"))
    )
    (net (code "39") (name "Net-(U2-VREG)") (class "Default")
      (node (ref "C5") (pin "1") (pinfunction "1_1") (pintype "passive"))
      (node (ref "C6") (pin "1") (pinfunction "1_1") (pintype "passive"))
      (node (ref "U2") (pin "4") (pinfunction "VREG_4") (pintype "bidirectional"))
    )
    (net (code "40") (name "VCC") (class "Default")
      (node (ref "C1") (pin "1") (pinfunction "1_1") (pintype "passive"))
      (node (ref "C2") (pin "1") (pinfunction "1_1") (pintype "passive"))
      (node (ref "C3") (pin "1") (pinfunction "1_1") (pintype "passive"))
      (node (ref "C4") (pin "1") (pinfunction "1_1") (pintype "passive"))
      (node (ref "R1") (pin "2") (pinfunction "2_2") (pintype "passive"))
      (node (ref "SJ1") (pin "2") (pinfunction "2_2") (pintype "passive"))
      (node (ref "SJ2") (pin "2") (pinfunction "2_2") (pintype "passive"))
      (node (ref "SJ3") (pin "2") (pinfunction "2_2") (pintype "passive"))
      (node (ref "SJ4") (pin "2") (pinfunction "2_2") (pintype "passive"))
      (node (ref "TP1") (pin "TP") (pinfunction "TP_TP") (pintype "input"))
      (node (ref "U1") (pin "19") (pinfunction "V+_19") (pintype "power_in"))
      (node (ref "U2") (pin "5") (pinfunction "VDDHI_5") (pintype "bidirectional"))
    )
  )
)
